# CELL_SENSE.net
KiCad netlist of a schematic drawn in Altium Designer
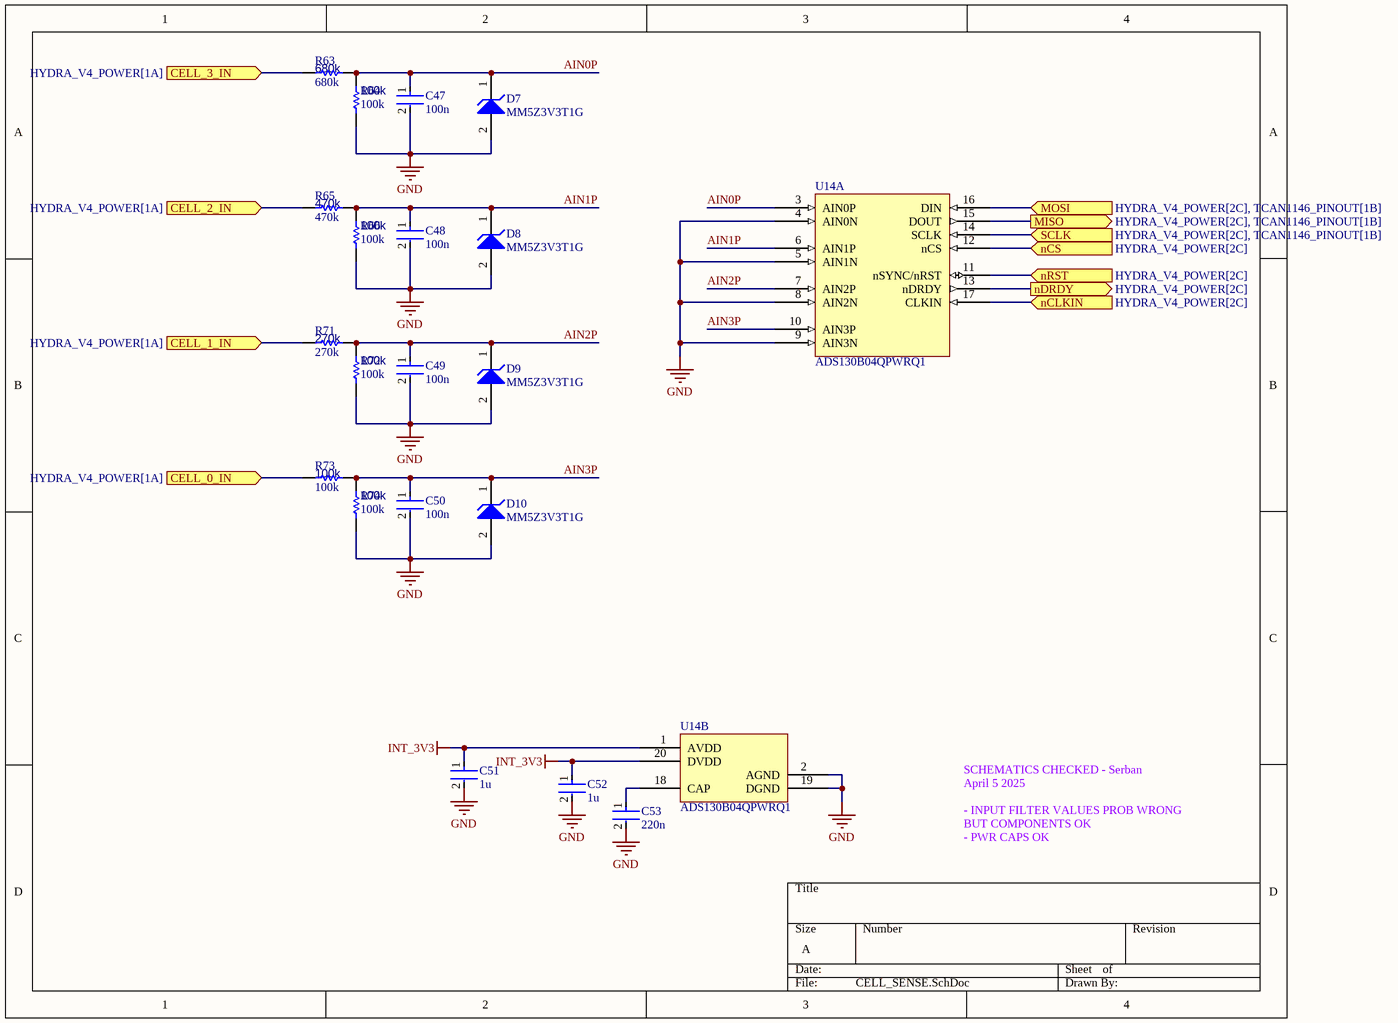
[diagram p0: CELL_SENSE.SchDoc]

(export (version "E")
  (design (tool "Eeschema 10.0.6"))
  (components
    (comp (ref "C47")
      (value "100n")
      (footprint "FP-0402-L_1_0_0_05-W_0_5-IPC_A")
      (description "LARGE PADS, 0402 CAP, CHANGE COMMENT TO MATCH REAL P/N")
      (libsource (lib "Space Concordia") (part "b4654b650e69147ec39a6b967a45e02"))
    )
    (comp (ref "C48")
      (value "100n")
      (footprint "FP-0402-L_1_0_0_05-W_0_5-IPC_A")
      (description "LARGE PADS, 0402 CAP, CHANGE COMMENT TO MATCH REAL P/N")
      (libsource (lib "Space Concordia") (part "b4654b650e69147ec39a6b967a45e02"))
    )
    (comp (ref "C49")
      (value "100n")
      (footprint "FP-0402-L_1_0_0_05-W_0_5-IPC_A")
      (description "LARGE PADS, 0402 CAP, CHANGE COMMENT TO MATCH REAL P/N")
      (libsource (lib "Space Concordia") (part "b4654b650e69147ec39a6b967a45e02"))
    )
    (comp (ref "C50")
      (value "100n")
      (footprint "FP-0402-L_1_0_0_05-W_0_5-IPC_A")
      (description "LARGE PADS, 0402 CAP, CHANGE COMMENT TO MATCH REAL P/N")
      (libsource (lib "Space Concordia") (part "b4654b650e69147ec39a6b967a45e02"))
    )
    (comp (ref "C51")
      (value "1u")
      (footprint "FP-0402-L_1_0_0_05-W_0_5-IPC_A")
      (description "LARGE PADS, 0402 CAP, CHANGE COMMENT TO MATCH REAL P/N")
      (libsource (lib "Space Concordia") (part "b4654b650e69147ec39a6b967a45e02"))
    )
    (comp (ref "C52")
      (value "1u")
      (footprint "FP-0402-L_1_0_0_05-W_0_5-IPC_A")
      (description "LARGE PADS, 0402 CAP, CHANGE COMMENT TO MATCH REAL P/N")
      (libsource (lib "Space Concordia") (part "b4654b650e69147ec39a6b967a45e02"))
    )
    (comp (ref "C53")
      (value "220n")
      (footprint "FP-0402-L_1_0_0_05-W_0_5-IPC_A")
      (description "LARGE PADS, 0402 CAP, CHANGE COMMENT TO MATCH REAL P/N")
      (libsource (lib "Space Concordia") (part "b4654b650e69147ec39a6b967a45e02"))
    )
    (comp (ref "D7")
      (value "MM5Z3V3T1G")
      (footprint "ONSC-SOD-523-2-502-01_V")
      (description "Zener Voltage Regulator, 500 mW, 2-Pin SOD-523, Pb-Free, Tape and Reel")
      (fields (field (name "MANUFACTURER") "On Semiconductor"))
      (libsource (lib "Altium Content Vault") (part "ONSC-K1A2-2"))
    )
    (comp (ref "D8")
      (value "MM5Z3V3T1G")
      (footprint "ONSC-SOD-523-2-502-01_V")
      (description "Zener Voltage Regulator, 500 mW, 2-Pin SOD-523, Pb-Free, Tape and Reel")
      (fields (field (name "MANUFACTURER") "On Semiconductor"))
      (libsource (lib "Altium Content Vault") (part "ONSC-K1A2-2"))
    )
    (comp (ref "D9")
      (value "MM5Z3V3T1G")
      (footprint "ONSC-SOD-523-2-502-01_V")
      (description "Zener Voltage Regulator, 500 mW, 2-Pin SOD-523, Pb-Free, Tape and Reel")
      (fields (field (name "MANUFACTURER") "On Semiconductor"))
      (libsource (lib "Altium Content Vault") (part "ONSC-K1A2-2"))
    )
    (comp (ref "D10")
      (value "MM5Z3V3T1G")
      (footprint "ONSC-SOD-523-2-502-01_V")
      (description "Zener Voltage Regulator, 500 mW, 2-Pin SOD-523, Pb-Free, Tape and Reel")
      (fields (field (name "MANUFACTURER") "On Semiconductor"))
      (libsource (lib "Altium Content Vault") (part "ONSC-K1A2-2"))
    )
    (comp (ref "R63")
      (value "680k")
      (footprint "R0603B")
      (description "Resistor")
      (fields (field (name "ALTIUM_VALUE") "680k"))
      (libsource (lib "Space Concordia") (part "Resistor"))
    )
    (comp (ref "R64")
      (value "100k")
      (footprint "R0603B")
      (description "Resistor")
      (fields (field (name "ALTIUM_VALUE") "100k"))
      (libsource (lib "Space Concordia") (part "Resistor"))
    )
    (comp (ref "R65")
      (value "470k")
      (footprint "R0603B")
      (description "Resistor")
      (fields (field (name "ALTIUM_VALUE") "470k"))
      (libsource (lib "Space Concordia") (part "Resistor"))
    )
    (comp (ref "R66")
      (value "100k")
      (footprint "R0603B")
      (description "Resistor")
      (fields (field (name "ALTIUM_VALUE") "100k"))
      (libsource (lib "Space Concordia") (part "Resistor"))
    )
    (comp (ref "R71")
      (value "270k")
      (footprint "R0603B")
      (description "Resistor")
      (fields (field (name "ALTIUM_VALUE") "270k"))
      (libsource (lib "Space Concordia") (part "Resistor"))
    )
    (comp (ref "R72")
      (value "100k")
      (footprint "R0603B")
      (description "Resistor")
      (fields (field (name "ALTIUM_VALUE") "100k"))
      (libsource (lib "Space Concordia") (part "Resistor"))
    )
    (comp (ref "R73")
      (value "100k")
      (footprint "R0603B")
      (description "Resistor")
      (fields (field (name "ALTIUM_VALUE") "100k"))
      (libsource (lib "Space Concordia") (part "Resistor"))
    )
    (comp (ref "R74")
      (value "100k")
      (footprint "R0603B")
      (description "Resistor")
      (fields (field (name "ALTIUM_VALUE") "100k"))
      (libsource (lib "Space Concordia") (part "Resistor"))
    )
    (comp (ref "U14")
      (value "ADS130B04QPWRQ1")
      (footprint "TSOP65P640X120-20N")
      (libsource (lib "Space Concordia") (part "ADS130B04QPWRQ1"))
    )
  )
  (nets
    (net (code "1") (name "/AIN0P") (class "Default")
      (node (ref "C47") (pin "1") (pinfunction "1_1") (pintype "passive"))
      (node (ref "D7") (pin "1") (pinfunction "K_1") (pintype "passive"))
      (node (ref "R63") (pin "1") (pinfunction "1_1") (pintype "passive"))
      (node (ref "R64") (pin "1") (pinfunction "1_1") (pintype "passive"))
      (node (ref "U14") (pin "3") (pinfunction "AIN0P_3") (pintype "input"))
    )
    (net (code "2") (name "/AIN1P") (class "Default")
      (node (ref "C48") (pin "1") (pinfunction "1_1") (pintype "passive"))
      (node (ref "D8") (pin "1") (pinfunction "K_1") (pintype "passive"))
      (node (ref "R65") (pin "1") (pinfunction "1_1") (pintype "passive"))
      (node (ref "R66") (pin "1") (pinfunction "1_1") (pintype "passive"))
      (node (ref "U14") (pin "6") (pinfunction "AIN1P_6") (pintype "input"))
    )
    (net (code "3") (name "/AIN2P") (class "Default")
      (node (ref "C49") (pin "1") (pinfunction "1_1") (pintype "passive"))
      (node (ref "D9") (pin "1") (pinfunction "K_1") (pintype "passive"))
      (node (ref "R71") (pin "1") (pinfunction "1_1") (pintype "passive"))
      (node (ref "R72") (pin "1") (pinfunction "1_1") (pintype "passive"))
      (node (ref "U14") (pin "7") (pinfunction "AIN2P_7") (pintype "input"))
    )
    (net (code "4") (name "/AIN3P") (class "Default")
      (node (ref "C50") (pin "1") (pinfunction "1_1") (pintype "passive"))
      (node (ref "D10") (pin "1") (pinfunction "K_1") (pintype "passive"))
      (node (ref "R73") (pin "1") (pinfunction "1_1") (pintype "passive"))
      (node (ref "R74") (pin "1") (pinfunction "1_1") (pintype "passive"))
      (node (ref "U14") (pin "10") (pinfunction "AIN3P_10") (pintype "input"))
    )
    (net (code "5") (name "/CELL_0_IN") (class "Default")
      (node (ref "R73") (pin "2") (pinfunction "2_2") (pintype "passive"))
    )
    (net (code "6") (name "/CELL_1_IN") (class "Default")
      (node (ref "R71") (pin "2") (pinfunction "2_2") (pintype "passive"))
    )
    (net (code "7") (name "/CELL_2_IN") (class "Default")
      (node (ref "R65") (pin "2") (pinfunction "2_2") (pintype "passive"))
    )
    (net (code "8") (name "/CELL_3_IN") (class "Default")
      (node (ref "R63") (pin "2") (pinfunction "2_2") (pintype "passive"))
    )
    (net (code "9") (name "/MISO") (class "Default")
      (node (ref "U14") (pin "15") (pinfunction "DOUT_15") (pintype "output"))
    )
    (net (code "10") (name "/MOSI") (class "Default")
      (node (ref "U14") (pin "16") (pinfunction "DIN_16") (pintype "input"))
    )
    (net (code "11") (name "/SCLK") (class "Default")
      (node (ref "U14") (pin "14") (pinfunction "SCLK_14") (pintype "input"))
    )
    (net (code "12") (name "/nCLKIN") (class "Default")
      (node (ref "U14") (pin "17") (pinfunction "CLKIN_17") (pintype "input"))
    )
    (net (code "13") (name "/nCS") (class "Default")
      (node (ref "U14") (pin "12") (pinfunction "nCS_12") (pintype "input"))
    )
    (net (code "14") (name "/nDRDY") (class "Default")
      (node (ref "U14") (pin "13") (pinfunction "nDRDY_13") (pintype "output"))
    )
    (net (code "15") (name "/nRST") (class "Default")
      (node (ref "U14") (pin "11") (pinfunction "nSYNC/nRST_11") (pintype "bidirectional"))
    )
    (net (code "16") (name "GND") (class "Default")
      (node (ref "C47") (pin "2") (pinfunction "2_2") (pintype "passive"))
      (node (ref "C48") (pin "2") (pinfunction "2_2") (pintype "passive"))
      (node (ref "C49") (pin "2") (pinfunction "2_2") (pintype "passive"))
      (node (ref "C50") (pin "2") (pinfunction "2_2") (pintype "passive"))
      (node (ref "C51") (pin "2") (pinfunction "2_2") (pintype "passive"))
      (node (ref "C52") (pin "2") (pinfunction "2_2") (pintype "passive"))
      (node (ref "C53") (pin "2") (pinfunction "2_2") (pintype "passive"))
      (node (ref "D10") (pin "2") (pinfunction "A_2") (pintype "passive"))
      (node (ref "D7") (pin "2") (pinfunction "A_2") (pintype "passive"))
      (node (ref "D8") (pin "2") (pinfunction "A_2") (pintype "passive"))
      (node (ref "D9") (pin "2") (pinfunction "A_2") (pintype "passive"))
      (node (ref "R64") (pin "2") (pinfunction "2_2") (pintype "passive"))
      (node (ref "R66") (pin "2") (pinfunction "2_2") (pintype "passive"))
      (node (ref "R72") (pin "2") (pinfunction "2_2") (pintype "passive"))
      (node (ref "R74") (pin "2") (pinfunction "2_2") (pintype "passive"))
      (node (ref "U14") (pin "19") (pinfunction "DGND_19") (pintype "power_in"))
      (node (ref "U14") (pin "2") (pinfunction "AGND_2") (pintype "power_in"))
      (node (ref "U14") (pin "4") (pinfunction "AIN0N_4") (pintype "input"))
      (node (ref "U14") (pin "5") (pinfunction "AIN1N_5") (pintype "input"))
      (node (ref "U14") (pin "8") (pinfunction "AIN2N_8") (pintype "input"))
      (node (ref "U14") (pin "9") (pinfunction "AIN3N_9") (pintype "input"))
    )
    (net (code "17") (name "INT_3V3") (class "Default")
      (node (ref "C51") (pin "1") (pinfunction "1_1") (pintype "passive"))
      (node (ref "C52") (pin "1") (pinfunction "1_1") (pintype "passive"))
      (node (ref "U14") (pin "1") (pinfunction "AVDD_1") (pintype "power_in"))
      (node (ref "U14") (pin "20") (pinfunction "DVDD_20") (pintype "power_in"))
    )
    (net (code "18") (name "Net-(U14B-CAP)") (class "Default")
      (node (ref "C53") (pin "1") (pinfunction "1_1") (pintype "passive"))
      (node (ref "U14") (pin "18") (pinfunction "CAP_18") (pintype "power_in"))
    )
  )
)
